# energy_monitor.net
KiCad netlist of a schematic drawn in EAGLE
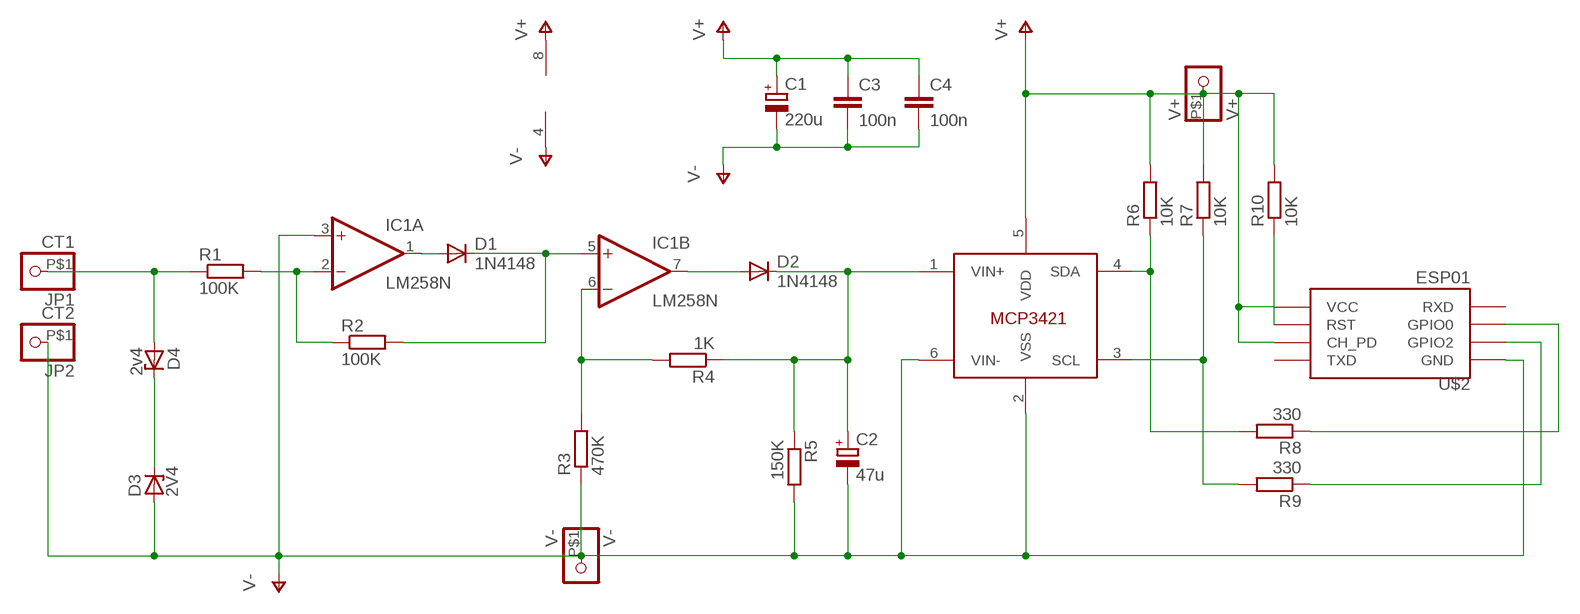
[diagram p0: schematic, sheet 1]

(export (version "E")
  (design (tool "Eeschema 10.0.6"))
  (components
    (comp (ref "C1")
      (value "220u")
      (footprint "eagle-import:E2,5-6")
      (libsource (lib "eagle-import") (part "CPOL-EUE2.5-6"))
    )
    (comp (ref "C2")
      (value "47u")
      (footprint "eagle-import:E2-4")
      (libsource (lib "eagle-import") (part "CPOL-EUE2-4"))
    )
    (comp (ref "C3")
      (value "100n")
      (footprint "eagle-import:C050-045X075")
      (libsource (lib "eagle-import") (part "C-EU050-045X075"))
    )
    (comp (ref "C4")
      (value "100n")
      (footprint "eagle-import:C050-045X075")
      (libsource (lib "eagle-import") (part "C-EU050-045X075"))
    )
    (comp (ref "D1")
      (value "1N4148")
      (footprint "eagle-import:DO35-7")
      (libsource (lib "eagle-import") (part "1N4148DO35-7"))
    )
    (comp (ref "D2")
      (value "1N4148")
      (footprint "eagle-import:DO35-7")
      (libsource (lib "eagle-import") (part "1N4148DO35-7"))
    )
    (comp (ref "D3")
      (value "2V4")
      (footprint "eagle-import:DO34Z7")
      (libsource (lib "eagle-import") (part "ZENER-DIODEDO34-7"))
    )
    (comp (ref "D4")
      (value "2v4")
      (footprint "eagle-import:DO34Z7")
      (libsource (lib "eagle-import") (part "ZENER-DIODEDO34-7"))
    )
    (comp (ref "IC1")
      (value "LM258N")
      (footprint "eagle-import:DIL08")
      (libsource (lib "eagle-import") (part "1458NLM"))
    )
    (comp (ref "JP1")
      (value "CT1")
      (footprint "eagle-import:1X1-BIGPOGO")
      (libsource (lib "eagle-import") (part "PINHD-1X1-BIGPOGO"))
    )
    (comp (ref "JP2")
      (value "CT2")
      (footprint "eagle-import:1X1-BIGPOGO")
      (libsource (lib "eagle-import") (part "PINHD-1X1-BIGPOGO"))
    )
    (comp (ref "R1")
      (value "100K")
      (footprint "eagle-import:0204_7")
      (libsource (lib "eagle-import") (part "R-EU_0204/7"))
    )
    (comp (ref "R2")
      (value "100K")
      (footprint "eagle-import:0204_7")
      (libsource (lib "eagle-import") (part "R-EU_0204/7"))
    )
    (comp (ref "R3")
      (value "470K")
      (footprint "eagle-import:0204_7")
      (libsource (lib "eagle-import") (part "R-EU_0204/7"))
    )
    (comp (ref "R4")
      (value "1K")
      (footprint "eagle-import:0204_7")
      (libsource (lib "eagle-import") (part "R-EU_0204/7"))
    )
    (comp (ref "R5")
      (value "150K")
      (footprint "eagle-import:0204_7")
      (libsource (lib "eagle-import") (part "R-EU_0204/7"))
    )
    (comp (ref "R6")
      (value "10K")
      (footprint "eagle-import:0204_7")
      (libsource (lib "eagle-import") (part "R-EU_0204/7"))
    )
    (comp (ref "R7")
      (value "10K")
      (footprint "eagle-import:0204_7")
      (libsource (lib "eagle-import") (part "R-EU_0204/7"))
    )
    (comp (ref "R8")
      (value "330")
      (footprint "eagle-import:0204_7")
      (libsource (lib "eagle-import") (part "R-EU_0204/7"))
    )
    (comp (ref "R9")
      (value "330")
      (footprint "eagle-import:0204_7")
      (libsource (lib "eagle-import") (part "R-EU_0204/7"))
    )
    (comp (ref "R10")
      (value "10K")
      (footprint "eagle-import:0204_7")
      (libsource (lib "eagle-import") (part "R-EU_0204/7"))
    )
    (comp (ref "U$1")
      (value "MCP3421ADAPTER")
      (footprint "eagle-import:DIL06")
      (libsource (lib "eagle-import") (part "MCP3421ADAPTER"))
    )
    (comp (ref "U$2")
      (value "ESP01")
      (footprint "eagle-import:ESP01")
      (libsource (lib "eagle-import") (part "ESP01"))
    )
    (comp (ref "V+")
      (value "V+")
      (footprint "eagle-import:1X1-BIGPOGO")
      (libsource (lib "eagle-import") (part "PINHD-1X1-BIGPOGO"))
    )
    (comp (ref "V-")
      (value "V-")
      (footprint "eagle-import:1X1-BIGPOGO")
      (libsource (lib "eagle-import") (part "PINHD-1X1-BIGPOGO"))
    )
  )
  (nets
    (net (code "1") (name "Net-(D3-PadC)") (class "Default")
      (node (ref "D3") (pin "C") (pinfunction "C_C") (pintype "passive"))
      (node (ref "D4") (pin "C") (pinfunction "C_C") (pintype "passive"))
    )
    (net (code "2") (name "Net-(IC1A--IN)") (class "Default")
      (node (ref "IC1") (pin "2") (pinfunction "-IN_2") (pintype "input"))
      (node (ref "R1") (pin "2") (pinfunction "2_2") (pintype "passive"))
      (node (ref "R2") (pin "1") (pinfunction "1_1") (pintype "passive"))
    )
    (net (code "3") (name "Net-(IC1A-OUT)") (class "Default")
      (node (ref "D1") (pin "A") (pinfunction "A_A") (pintype "passive"))
      (node (ref "IC1") (pin "1") (pinfunction "OUT_1") (pintype "output"))
    )
    (net (code "4") (name "Net-(IC1B-+IN)") (class "Default")
      (node (ref "D1") (pin "C") (pinfunction "C_C") (pintype "passive"))
      (node (ref "IC1") (pin "5") (pinfunction "+IN_5") (pintype "input"))
      (node (ref "R2") (pin "2") (pinfunction "2_2") (pintype "passive"))
    )
    (net (code "5") (name "Net-(IC1B--IN)") (class "Default")
      (node (ref "IC1") (pin "6") (pinfunction "-IN_6") (pintype "input"))
      (node (ref "R3") (pin "2") (pinfunction "2_2") (pintype "passive"))
      (node (ref "R4") (pin "2") (pinfunction "2_2") (pintype "passive"))
    )
    (net (code "6") (name "Net-(IC1B-OUT)") (class "Default")
      (node (ref "D2") (pin "A") (pinfunction "A_A") (pintype "passive"))
      (node (ref "IC1") (pin "7") (pinfunction "OUT_7") (pintype "output"))
    )
    (net (code "7") (name "Net-(JP1-1)") (class "Default")
      (node (ref "D4") (pin "A") (pinfunction "A_A") (pintype "passive"))
      (node (ref "JP1") (pin "P$1") (pinfunction "1_P$1") (pintype "passive"))
      (node (ref "R1") (pin "1") (pinfunction "1_1") (pintype "passive"))
    )
    (net (code "8") (name "Net-(R8-Pad1)") (class "Default")
      (node (ref "R8") (pin "1") (pinfunction "1_1") (pintype "passive"))
      (node (ref "U$2") (pin "GPIO0") (pinfunction "GPIO0_GPIO0") (pintype "bidirectional"))
    )
    (net (code "9") (name "Net-(R9-Pad1)") (class "Default")
      (node (ref "R9") (pin "1") (pinfunction "1_1") (pintype "passive"))
      (node (ref "U$2") (pin "GPIO2") (pinfunction "GPIO2_GPIO2") (pintype "bidirectional"))
    )
    (net (code "10") (name "Net-(R10-Pad1)") (class "Default")
      (node (ref "R10") (pin "1") (pinfunction "1_1") (pintype "passive"))
      (node (ref "U$2") (pin "RST") (pinfunction "RST_RST") (pintype "bidirectional"))
    )
    (net (code "11") (name "Net-(U$1-SCL)") (class "Default")
      (node (ref "R7") (pin "1") (pinfunction "1_1") (pintype "passive"))
      (node (ref "R9") (pin "2") (pinfunction "2_2") (pintype "passive"))
      (node (ref "U$1") (pin "3") (pinfunction "SCL_3") (pintype "bidirectional"))
    )
    (net (code "12") (name "Net-(U$1-SDA)") (class "Default")
      (node (ref "R6") (pin "1") (pinfunction "1_1") (pintype "passive"))
      (node (ref "R8") (pin "2") (pinfunction "2_2") (pintype "passive"))
      (node (ref "U$1") (pin "4") (pinfunction "SDA_4") (pintype "bidirectional"))
    )
    (net (code "13") (name "Net-(U$1-VIN+)") (class "Default")
      (node (ref "C2") (pin "+") (pinfunction "+_+") (pintype "passive"))
      (node (ref "D2") (pin "C") (pinfunction "C_C") (pintype "passive"))
      (node (ref "R4") (pin "1") (pinfunction "1_1") (pintype "passive"))
      (node (ref "R5") (pin "1") (pinfunction "1_1") (pintype "passive"))
      (node (ref "U$1") (pin "1") (pinfunction "VIN+_1") (pintype "bidirectional"))
    )
    (net (code "14") (name "V+") (class "Default")
      (node (ref "C1") (pin "+") (pinfunction "+_+") (pintype "passive"))
      (node (ref "C3") (pin "1") (pinfunction "1_1") (pintype "passive"))
      (node (ref "C4") (pin "1") (pinfunction "1_1") (pintype "passive"))
      (node (ref "IC1") (pin "8") (pinfunction "V+_8") (pintype "power_in"))
      (node (ref "R10") (pin "2") (pinfunction "2_2") (pintype "passive"))
      (node (ref "R6") (pin "2") (pinfunction "2_2") (pintype "passive"))
      (node (ref "R7") (pin "2") (pinfunction "2_2") (pintype "passive"))
      (node (ref "U$1") (pin "5") (pinfunction "VDD_5") (pintype "bidirectional"))
      (node (ref "U$2") (pin "CH_PD") (pinfunction "CH_PD_CH_PD") (pintype "bidirectional"))
      (node (ref "U$2") (pin "VCC") (pinfunction "VCC_VCC") (pintype "bidirectional"))
      (node (ref "V+") (pin "P$1") (pinfunction "1_P$1") (pintype "passive"))
    )
    (net (code "15") (name "V-") (class "Default")
      (node (ref "C1") (pin "-") (pinfunction "-_-") (pintype "passive"))
      (node (ref "C2") (pin "-") (pinfunction "-_-") (pintype "passive"))
      (node (ref "C3") (pin "2") (pinfunction "2_2") (pintype "passive"))
      (node (ref "C4") (pin "2") (pinfunction "2_2") (pintype "passive"))
      (node (ref "D3") (pin "A") (pinfunction "A_A") (pintype "passive"))
      (node (ref "IC1") (pin "3") (pinfunction "+IN_3") (pintype "input"))
      (node (ref "IC1") (pin "4") (pinfunction "V-_4") (pintype "power_in"))
      (node (ref "JP2") (pin "P$1") (pinfunction "1_P$1") (pintype "passive"))
      (node (ref "R3") (pin "1") (pinfunction "1_1") (pintype "passive"))
      (node (ref "R5") (pin "2") (pinfunction "2_2") (pintype "passive"))
      (node (ref "U$1") (pin "2") (pinfunction "VSS_2") (pintype "bidirectional"))
      (node (ref "U$1") (pin "6") (pinfunction "VIN-_6") (pintype "bidirectional"))
      (node (ref "U$2") (pin "GND") (pinfunction "GND_GND") (pintype "bidirectional"))
      (node (ref "V-") (pin "P$1") (pinfunction "1_P$1") (pintype "passive"))
    )
    (net (code "16") (name "unconnected-(U$2-RXD-PadRX)") (class "Default")
      (node (ref "U$2") (pin "RX") (pinfunction "RXD_RX") (pintype "bidirectional"))
    )
    (net (code "17") (name "unconnected-(U$2-TXD-PadTX)") (class "Default")
      (node (ref "U$2") (pin "TX") (pinfunction "TXD_TX") (pintype "bidirectional"))
    )
  )
)
